# Sheet1.net
KiCad netlist of a schematic drawn in Altium Designer
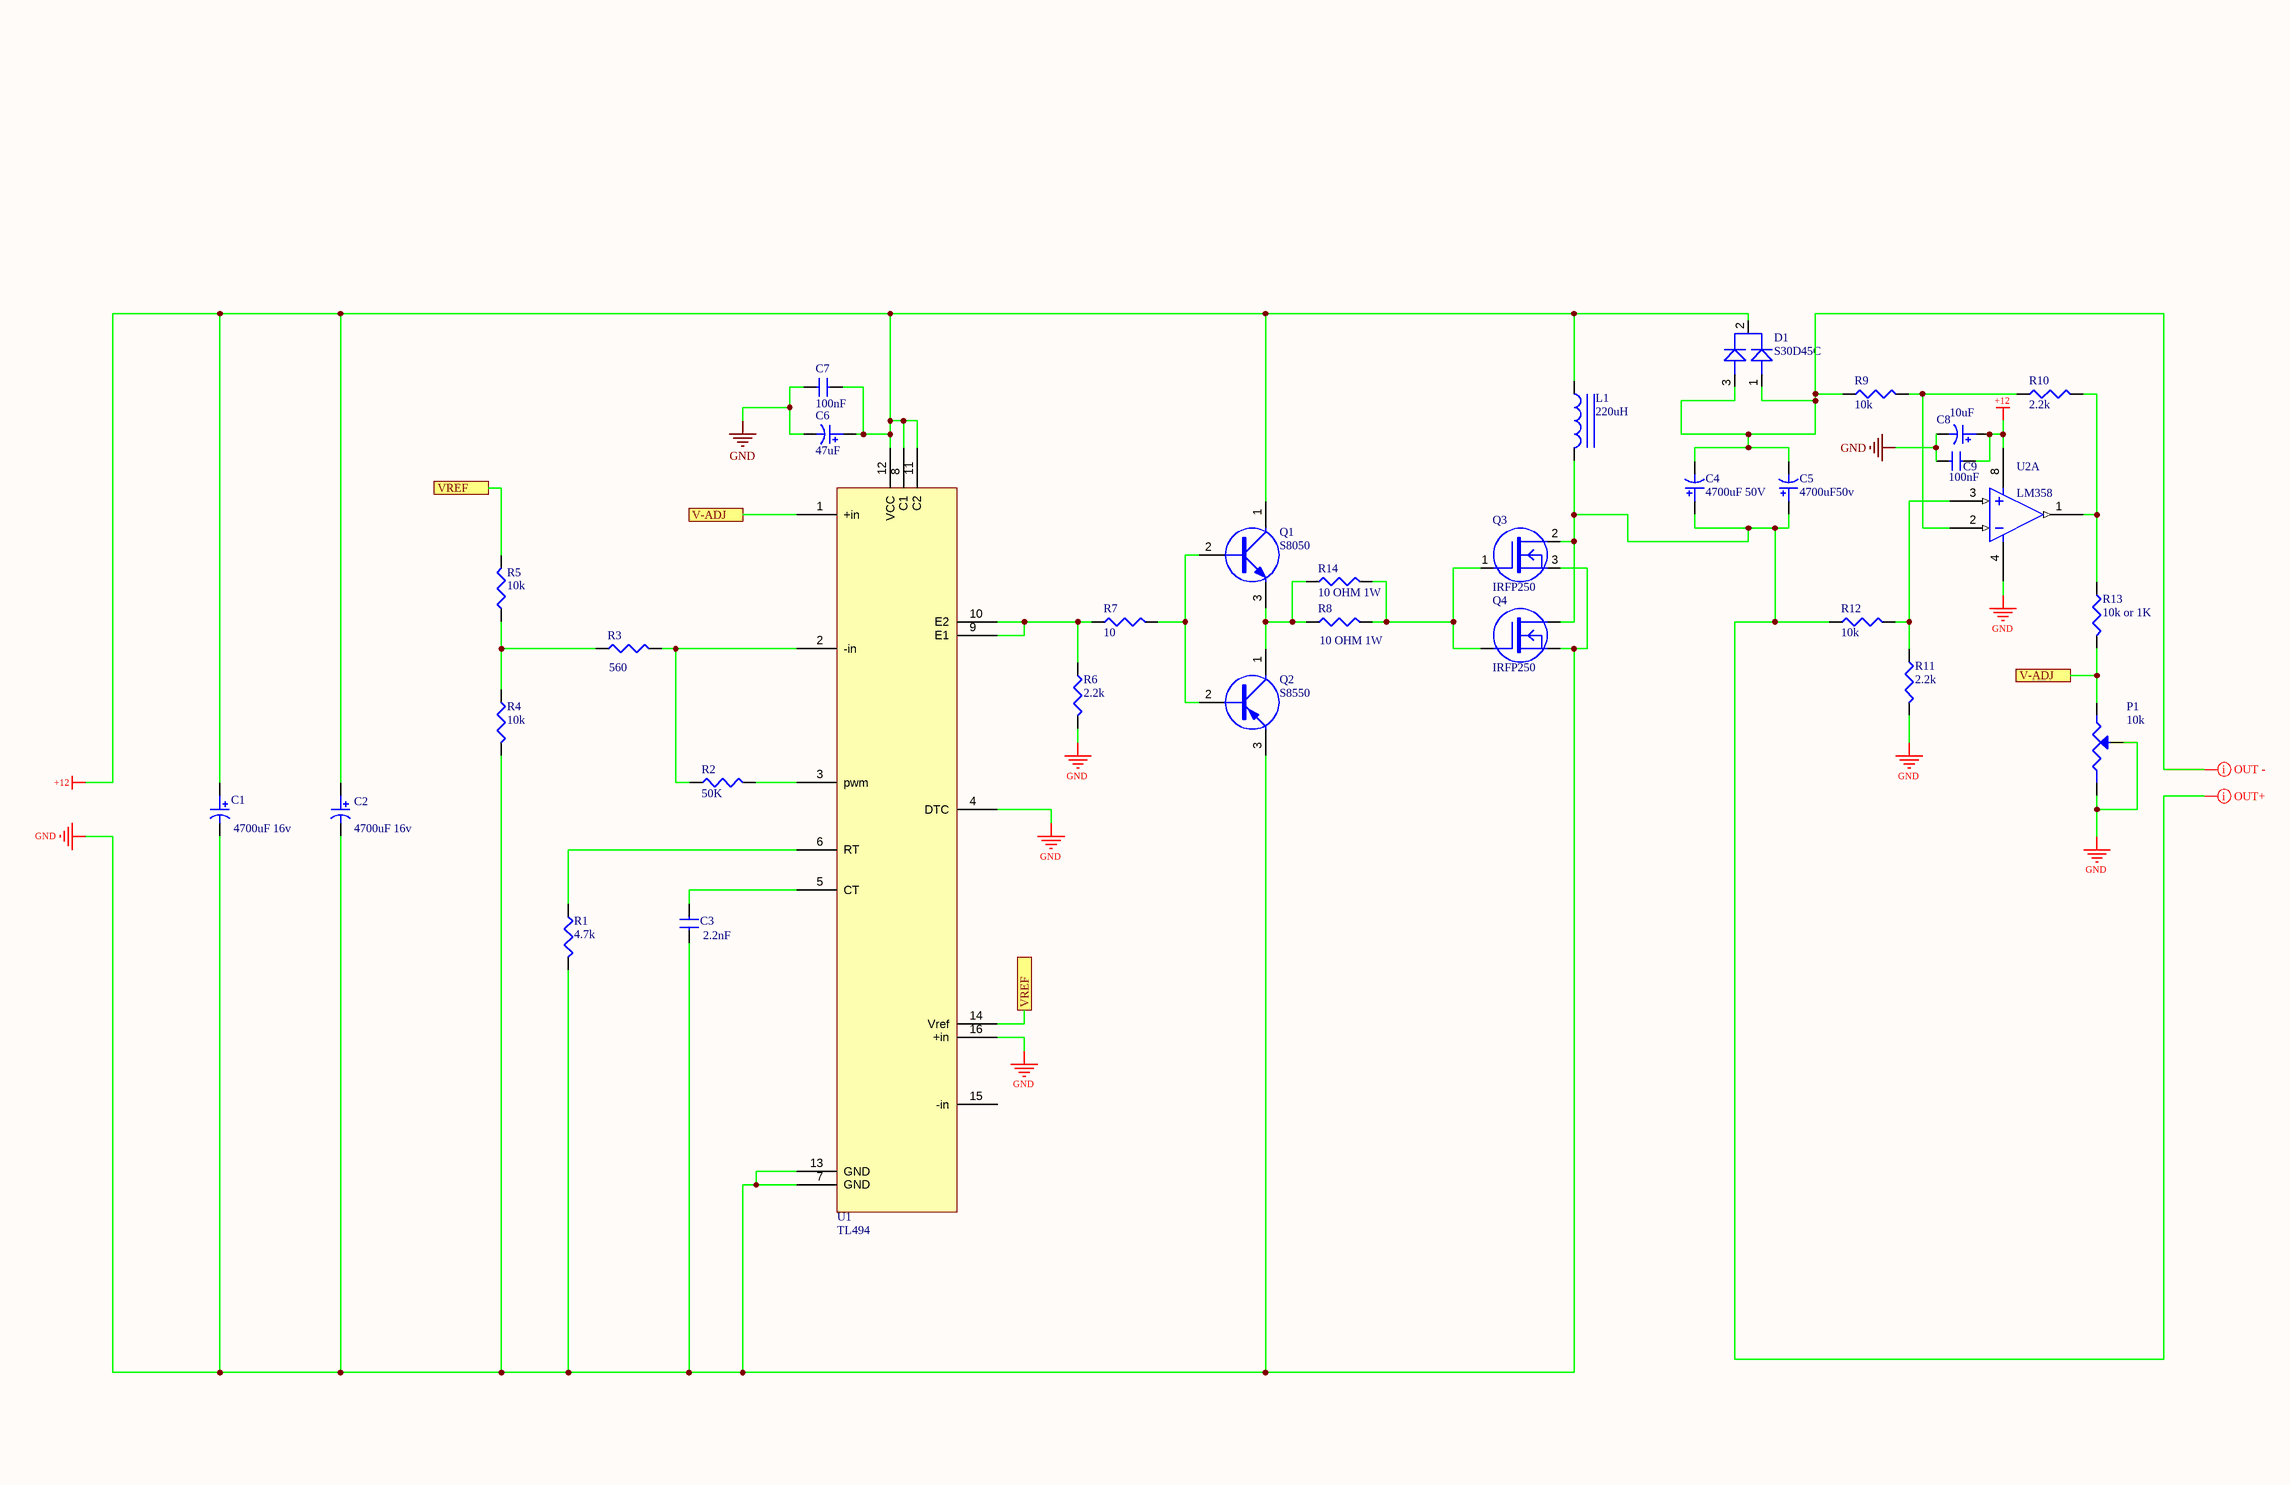
[diagram p0: Sheet1.SchDoc]

(export (version "E")
  (design (tool "Eeschema 10.0.6"))
  (components
    (comp (ref "C1")
      (value "4700uF 16v")
      (footprint "RB5-10.5")
      (libsource (lib "Integrated_Library1") (part "CAPACITOR POL"))
    )
    (comp (ref "C2")
      (value "4700uF 16v")
      (footprint "RB5-10.5")
      (libsource (lib "Integrated_Library1") (part "CAPACITOR POL"))
    )
    (comp (ref "C3")
      (value "2.2nF")
      (footprint "CAPR5-4X5")
      (libsource (lib "Integrated_Library1") (part "CAP"))
    )
    (comp (ref "C4")
      (value "4700uF 50V")
      (footprint "RB7.6-15")
      (libsource (lib "Integrated_Library1") (part "CAPACITOR POL"))
    )
    (comp (ref "C5")
      (value "4700uF50v")
      (footprint "RB7.6-15")
      (libsource (lib "Integrated_Library1") (part "CAPACITOR POL"))
    )
    (comp (ref "C6")
      (value "47uF")
      (footprint "CAPR5-4X5")
      (libsource (lib "Integrated_Library1") (part "CAPACITOR POL"))
    )
    (comp (ref "C7")
      (value "100nF")
      (footprint "CAPR5-4X5")
      (libsource (lib "Integrated_Library1") (part "CAP"))
    )
    (comp (ref "C8")
      (value "10uF")
      (footprint "CAPR5-4X5")
      (libsource (lib "Integrated_Library1") (part "CAPACITOR POL"))
    )
    (comp (ref "C9")
      (value "100nF")
      (footprint "CAPR5-4X5")
      (libsource (lib "Integrated_Library1") (part "CAP"))
    )
    (comp (ref "D1")
      (value "S30D45C")
      (footprint "TO-247")
      (libsource (lib "Integrated_Library1") (part "DIODE-DUAL"))
    )
    (comp (ref "L1")
      (value "220uH")
      (footprint "RB7.6-15")
      (libsource (lib "Integrated_Library1") (part "INDUCTOR IRON"))
    )
    (comp (ref "P1") (value "10k") (footprint "VR5") (libsource (lib "Integrated_Library1") (part "RES VAR")))
    (comp (ref "Q1")
      (value "S8050")
      (footprint "TO-220-AB")
      (libsource (lib "Integrated_Library1") (part "NPN3"))
    )
    (comp (ref "Q2")
      (value "S8550")
      (footprint "TO-220-AB")
      (libsource (lib "Integrated_Library1") (part "PNP3"))
    )
    (comp (ref "Q3")
      (value "IRFP250")
      (footprint "TO-247")
      (libsource (lib "Integrated_Library1") (part "MOSFET-N1"))
    )
    (comp (ref "Q4") (value "IRFP250") (footprint "TO-247") (libsource (lib "") (part "MOSFET-N1_1")))
    (comp (ref "R1")
      (value "4.7k")
      (footprint "AXIAL0.4")
      (libsource (lib "Integrated_Library1") (part "RES"))
    )
    (comp (ref "R2")
      (value "50K")
      (footprint "AXIAL0.4")
      (libsource (lib "Integrated_Library1") (part "RES"))
    )
    (comp (ref "R3")
      (value "560")
      (footprint "AXIAL0.4")
      (libsource (lib "Integrated_Library1") (part "RES"))
    )
    (comp (ref "R4")
      (value "10k")
      (footprint "AXIAL0.4")
      (libsource (lib "Integrated_Library1") (part "RES"))
    )
    (comp (ref "R5")
      (value "10k")
      (footprint "AXIAL0.4")
      (libsource (lib "Integrated_Library1") (part "RES"))
    )
    (comp (ref "R6")
      (value "2.2k")
      (footprint "AXIAL0.4")
      (libsource (lib "Integrated_Library1") (part "RES"))
    )
    (comp (ref "R7") (value "10") (footprint "AXIAL0.4") (libsource (lib "Integrated_Library1") (part "RES")))
    (comp (ref "R8")
      (value "10 OHM 1W")
      (footprint "AXIAL-0.6")
      (libsource (lib "Integrated_Library1") (part "RES"))
    )
    (comp (ref "R9")
      (value "10k")
      (footprint "AXIAL0.4")
      (libsource (lib "Integrated_Library1") (part "RES"))
    )
    (comp (ref "R10")
      (value "2.2k")
      (footprint "AXIAL0.4")
      (libsource (lib "Integrated_Library1") (part "RES"))
    )
    (comp (ref "R11")
      (value "2.2k")
      (footprint "AXIAL0.4")
      (libsource (lib "Integrated_Library1") (part "RES"))
    )
    (comp (ref "R12")
      (value "10k")
      (footprint "AXIAL0.4")
      (libsource (lib "Integrated_Library1") (part "RES"))
    )
    (comp (ref "R13")
      (value "10k or 1K")
      (footprint "AXIAL-0.6")
      (libsource (lib "Integrated_Library1") (part "RES"))
    )
    (comp (ref "R14")
      (value "10 OHM 1W")
      (footprint "AXIAL-0.6")
      (libsource (lib "Integrated_Library1") (part "RES"))
    )
    (comp (ref "U1")
      (value "TL494")
      (footprint "DIP16")
      (libsource (lib "Integrated_Library1") (part "TL494"))
    )
    (comp (ref "U2")
      (value "LM358")
      (footprint "DIP8")
      (libsource (lib "Integrated_Library1") (part "LM358"))
    )
  )
  (nets
    (net (code "1") (name "+12") (class "Default")
      (node (ref "C1") (pin "1") (pinfunction "1_1") (pintype "passive"))
      (node (ref "C2") (pin "1") (pinfunction "1_1") (pintype "passive"))
      (node (ref "C6") (pin "1") (pinfunction "1_1") (pintype "passive"))
      (node (ref "C7") (pin "2") (pinfunction "2_2") (pintype "passive"))
      (node (ref "C8") (pin "1") (pinfunction "1_1") (pintype "passive"))
      (node (ref "C9") (pin "2") (pinfunction "2_2") (pintype "passive"))
      (node (ref "D1") (pin "2") (pinfunction "2_2") (pintype "passive"))
      (node (ref "L1") (pin "1") (pinfunction "1_1") (pintype "passive"))
      (node (ref "Q1") (pin "1") (pinfunction "C_1") (pintype "passive"))
      (node (ref "U1") (pin "11") (pinfunction "C2_11") (pintype "passive"))
      (node (ref "U1") (pin "12") (pinfunction "VCC_12") (pintype "passive"))
      (node (ref "U1") (pin "8") (pinfunction "C1_8") (pintype "passive"))
      (node (ref "U2") (pin "8") (pinfunction "V-_8") (pintype "passive"))
    )
    (net (code "2") (name "/V-ADJ") (class "Default")
      (node (ref "P1") (pin "1") (pinfunction "1_1") (pintype "passive"))
      (node (ref "R13") (pin "2") (pinfunction "2_2") (pintype "passive"))
      (node (ref "U1") (pin "1") (pinfunction "+in_1") (pintype "passive"))
    )
    (net (code "3") (name "/VREF") (class "Default")
      (node (ref "R5") (pin "2") (pinfunction "2_2") (pintype "passive"))
      (node (ref "U1") (pin "14") (pinfunction "Vref_14") (pintype "passive"))
    )
    (net (code "4") (name "GND") (class "Default")
      (node (ref "C1") (pin "2") (pinfunction "2_2") (pintype "passive"))
      (node (ref "C2") (pin "2") (pinfunction "2_2") (pintype "passive"))
      (node (ref "C3") (pin "2") (pinfunction "2_2") (pintype "passive"))
      (node (ref "C6") (pin "2") (pinfunction "2_2") (pintype "passive"))
      (node (ref "C7") (pin "1") (pinfunction "1_1") (pintype "passive"))
      (node (ref "C8") (pin "2") (pinfunction "2_2") (pintype "passive"))
      (node (ref "C9") (pin "1") (pinfunction "1_1") (pintype "passive"))
      (node (ref "P1") (pin "2") (pinfunction "2_2") (pintype "passive"))
      (node (ref "P1") (pin "3") (pinfunction "3_3") (pintype "passive"))
      (node (ref "Q2") (pin "3") (pinfunction "E_3") (pintype "passive"))
      (node (ref "Q3") (pin "3") (pintype "passive"))
      (node (ref "Q4") (pin "3") (pintype "passive"))
      (node (ref "R1") (pin "2") (pinfunction "2_2") (pintype "passive"))
      (node (ref "R11") (pin "2") (pinfunction "2_2") (pintype "passive"))
      (node (ref "R4") (pin "2") (pinfunction "2_2") (pintype "passive"))
      (node (ref "R6") (pin "2") (pinfunction "2_2") (pintype "passive"))
      (node (ref "U1") (pin "13") (pinfunction "GND_13") (pintype "passive"))
      (node (ref "U1") (pin "16") (pinfunction "+in_16") (pintype "passive"))
      (node (ref "U1") (pin "4") (pinfunction "DTC_4") (pintype "passive"))
      (node (ref "U1") (pin "7") (pinfunction "GND_7") (pintype "passive"))
      (node (ref "U2") (pin "4") (pinfunction "V+_4") (pintype "passive"))
    )
    (net (code "5") (name "Net-(C4-Pad1)") (class "Default")
      (node (ref "C4") (pin "1") (pinfunction "1_1") (pintype "passive"))
      (node (ref "C5") (pin "1") (pinfunction "1_1") (pintype "passive"))
      (node (ref "L1") (pin "2") (pinfunction "2_2") (pintype "passive"))
      (node (ref "Q3") (pin "2") (pintype "passive"))
      (node (ref "Q4") (pin "2") (pintype "passive"))
      (node (ref "R12") (pin "1") (pinfunction "1_1") (pintype "passive"))
    )
    (net (code "6") (name "Net-(C4-Pad2)") (class "Default")
      (node (ref "C4") (pin "2") (pinfunction "2_2") (pintype "passive"))
      (node (ref "C5") (pin "2") (pinfunction "2_2") (pintype "passive"))
      (node (ref "D1") (pin "1") (pinfunction "1_1") (pintype "passive"))
      (node (ref "D1") (pin "3") (pinfunction "3_3") (pintype "passive"))
      (node (ref "R9") (pin "1") (pinfunction "1_1") (pintype "passive"))
    )
    (net (code "7") (name "Net-(Q1-B)") (class "Default")
      (node (ref "Q1") (pin "2") (pinfunction "B_2") (pintype "passive"))
      (node (ref "Q2") (pin "2") (pinfunction "B_2") (pintype "passive"))
      (node (ref "R7") (pin "2") (pinfunction "2_2") (pintype "passive"))
    )
    (net (code "8") (name "Net-(Q1-E)") (class "Default")
      (node (ref "Q1") (pin "3") (pinfunction "E_3") (pintype "passive"))
      (node (ref "Q2") (pin "1") (pinfunction "C_1") (pintype "passive"))
      (node (ref "R14") (pin "1") (pinfunction "1_1") (pintype "passive"))
      (node (ref "R8") (pin "1") (pinfunction "1_1") (pintype "passive"))
    )
    (net (code "9") (name "Net-(Q3-Pad1)") (class "Default")
      (node (ref "Q3") (pin "1") (pintype "passive"))
      (node (ref "Q4") (pin "1") (pintype "passive"))
      (node (ref "R14") (pin "2") (pinfunction "2_2") (pintype "passive"))
      (node (ref "R8") (pin "2") (pinfunction "2_2") (pintype "passive"))
    )
    (net (code "10") (name "Net-(R2-Pad1)") (class "Default")
      (node (ref "R2") (pin "1") (pinfunction "1_1") (pintype "passive"))
      (node (ref "R3") (pin "2") (pinfunction "2_2") (pintype "passive"))
      (node (ref "U1") (pin "2") (pinfunction "-in_2") (pintype "passive"))
    )
    (net (code "11") (name "Net-(R3-Pad1)") (class "Default")
      (node (ref "R3") (pin "1") (pinfunction "1_1") (pintype "passive"))
      (node (ref "R4") (pin "1") (pinfunction "1_1") (pintype "passive"))
      (node (ref "R5") (pin "1") (pinfunction "1_1") (pintype "passive"))
    )
    (net (code "12") (name "Net-(U1-CT)") (class "Default")
      (node (ref "C3") (pin "1") (pinfunction "1_1") (pintype "passive"))
      (node (ref "U1") (pin "5") (pinfunction "CT_5") (pintype "passive"))
    )
    (net (code "13") (name "Net-(U1-E1)") (class "Default")
      (node (ref "R6") (pin "1") (pinfunction "1_1") (pintype "passive"))
      (node (ref "R7") (pin "1") (pinfunction "1_1") (pintype "passive"))
      (node (ref "U1") (pin "10") (pinfunction "E2_10") (pintype "passive"))
      (node (ref "U1") (pin "9") (pinfunction "E1_9") (pintype "passive"))
    )
    (net (code "14") (name "Net-(U1-RT)") (class "Default")
      (node (ref "R1") (pin "1") (pinfunction "1_1") (pintype "passive"))
      (node (ref "U1") (pin "6") (pinfunction "RT_6") (pintype "passive"))
    )
    (net (code "15") (name "Net-(U1-pwm)") (class "Default")
      (node (ref "R2") (pin "2") (pinfunction "2_2") (pintype "passive"))
      (node (ref "U1") (pin "3") (pinfunction "pwm_3") (pintype "passive"))
    )
    (net (code "16") (name "Net-(U2A-+IN)") (class "Default")
      (node (ref "R11") (pin "1") (pinfunction "1_1") (pintype "passive"))
      (node (ref "R12") (pin "2") (pinfunction "2_2") (pintype "passive"))
      (node (ref "U2") (pin "3") (pinfunction "+IN_3") (pintype "input"))
    )
    (net (code "17") (name "Net-(U2A--IN)") (class "Default")
      (node (ref "R10") (pin "1") (pinfunction "1_1") (pintype "passive"))
      (node (ref "R9") (pin "2") (pinfunction "2_2") (pintype "passive"))
      (node (ref "U2") (pin "2") (pinfunction "-IN_2") (pintype "input"))
    )
    (net (code "18") (name "Net-(U2A-OUT)") (class "Default")
      (node (ref "R10") (pin "2") (pinfunction "2_2") (pintype "passive"))
      (node (ref "R13") (pin "1") (pinfunction "1_1") (pintype "passive"))
      (node (ref "U2") (pin "1") (pinfunction "OUT_1") (pintype "output"))
    )
    (net (code "19") (name "unconnected-(U1--in-Pad15)") (class "Default")
      (node (ref "U1") (pin "15") (pinfunction "-in_15") (pintype "passive"))
    )
  )
)
